# UART-Bluetooth.net
KiCad netlist of a schematic drawn in EAGLE
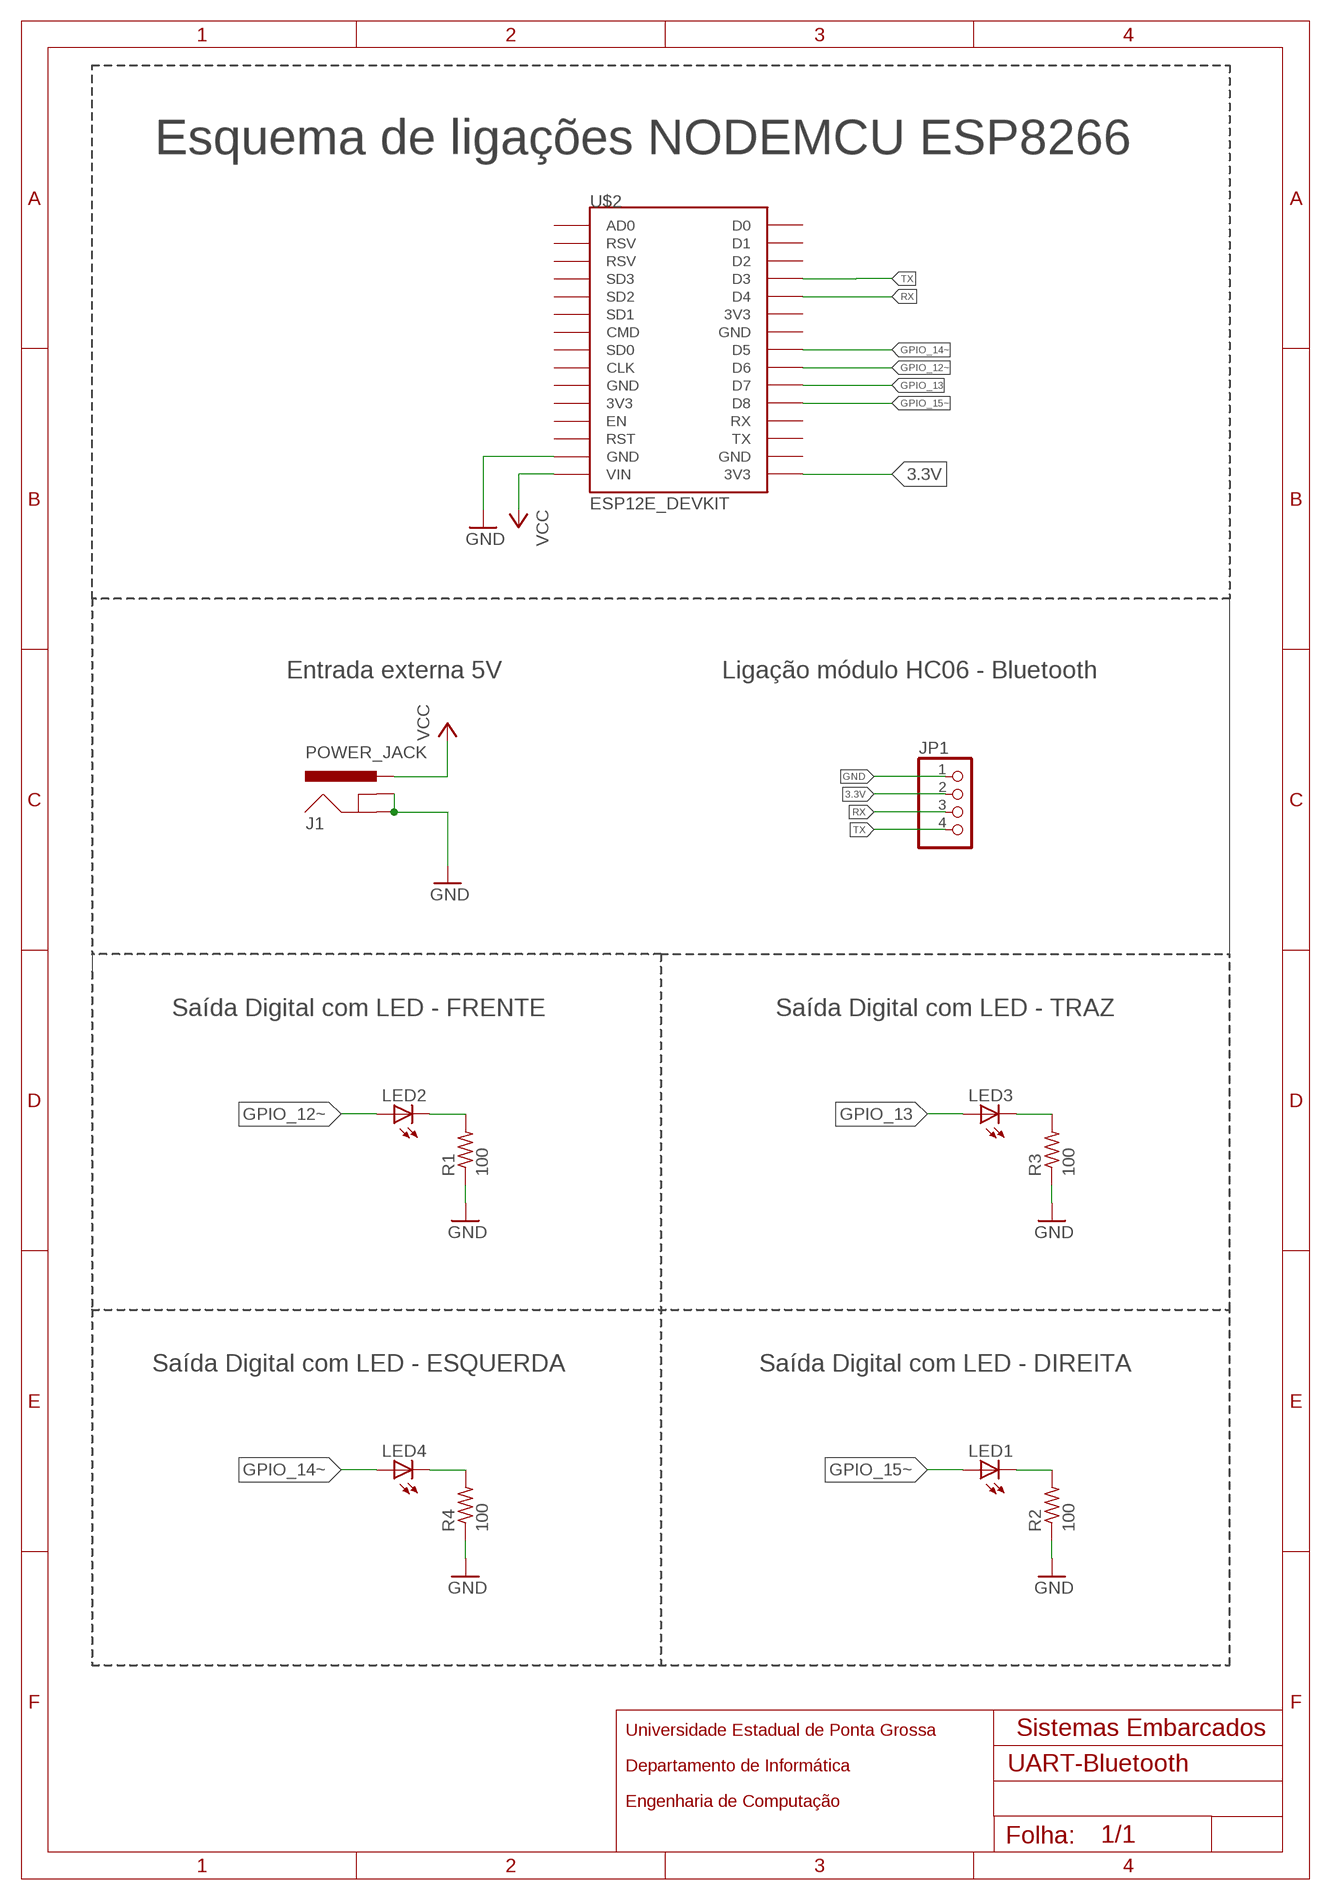
[diagram p0: schematic, sheet 1]

(export (version "E")
  (design (tool "Eeschema 10.0.6"))
  (components
    (comp (ref "J1")
      (value "POWER_JACK")
      (footprint "eagle-import:POWER_JACK_PTH")
      (libsource (lib "eagle-import") (part "POWER_JACK"))
    )
    (comp (ref "JP1")
      (value "PINHD-1X4")
      (footprint "eagle-import:1X04")
      (libsource (lib "eagle-import") (part "PINHD-1X4"))
    )
    (comp (ref "LED1")
      (value "LED5MM")
      (footprint "eagle-import:LED5MM")
      (libsource (lib "eagle-import") (part "LED5MM"))
    )
    (comp (ref "LED2")
      (value "LED5MM")
      (footprint "eagle-import:LED5MM")
      (libsource (lib "eagle-import") (part "LED5MM"))
    )
    (comp (ref "LED3")
      (value "LED5MM")
      (footprint "eagle-import:LED5MM")
      (libsource (lib "eagle-import") (part "LED5MM"))
    )
    (comp (ref "LED4")
      (value "LED5MM")
      (footprint "eagle-import:LED5MM")
      (libsource (lib "eagle-import") (part "LED5MM"))
    )
    (comp (ref "R1")
      (value "100")
      (footprint "eagle-import:0204_7")
      (libsource (lib "eagle-import") (part "R-US_0204/7"))
    )
    (comp (ref "R2")
      (value "100")
      (footprint "eagle-import:0204_7")
      (libsource (lib "eagle-import") (part "R-US_0204/7"))
    )
    (comp (ref "R3")
      (value "100")
      (footprint "eagle-import:0204_7")
      (libsource (lib "eagle-import") (part "R-US_0204/7"))
    )
    (comp (ref "R4")
      (value "100")
      (footprint "eagle-import:0204_7")
      (libsource (lib "eagle-import") (part "R-US_0204/7"))
    )
    (comp (ref "U$2")
      (value "ESP12E_DEVKIT")
      (footprint "eagle-import:ESP12E_DEVKIT")
      (libsource (lib "eagle-import") (part "ESP12E_DEVKIT"))
    )
  )
  (nets
    (net (code "1") (name "/GPIO_12~{}") (class "Default")
      (node (ref "LED2") (pin "A") (pinfunction "A_A") (pintype "passive"))
      (node (ref "U$2") (pin "D6") (pinfunction "D6_D6") (pintype "bidirectional"))
    )
    (net (code "2") (name "/GPIO_14~{}") (class "Default")
      (node (ref "LED4") (pin "A") (pinfunction "A_A") (pintype "passive"))
      (node (ref "U$2") (pin "D5") (pinfunction "D5_D5") (pintype "bidirectional"))
    )
    (net (code "3") (name "/GPIO_15~{}") (class "Default")
      (node (ref "LED1") (pin "A") (pinfunction "A_A") (pintype "passive"))
      (node (ref "U$2") (pin "D8") (pinfunction "D8_D8") (pintype "bidirectional"))
    )
    (net (code "4") (name "3.3V") (class "Default")
      (node (ref "JP1") (pin "2") (pinfunction "2_2") (pintype "passive"))
      (node (ref "U$2") (pin "3V3@2") (pinfunction "3V3_3V3@2") (pintype "bidirectional"))
    )
    (net (code "5") (name "GND") (class "Default")
      (node (ref "J1") (pin "GND") (pinfunction "GND_GND") (pintype "bidirectional"))
      (node (ref "J1") (pin "GNDBREAK") (pinfunction "GNDBREAK_GNDBREAK") (pintype "bidirectional"))
      (node (ref "JP1") (pin "1") (pinfunction "1_1") (pintype "passive"))
      (node (ref "R1") (pin "1") (pinfunction "1_1") (pintype "passive"))
      (node (ref "R2") (pin "1") (pinfunction "1_1") (pintype "passive"))
      (node (ref "R3") (pin "1") (pinfunction "1_1") (pintype "passive"))
      (node (ref "R4") (pin "1") (pinfunction "1_1") (pintype "passive"))
      (node (ref "U$2") (pin "GND@1") (pinfunction "GND_GND@1") (pintype "bidirectional"))
    )
    (net (code "6") (name "GPIO_13") (class "Default")
      (node (ref "LED3") (pin "A") (pinfunction "A_A") (pintype "passive"))
      (node (ref "U$2") (pin "D7") (pinfunction "D7_D7") (pintype "bidirectional"))
    )
    (net (code "7") (name "Net-(LED1-C)") (class "Default")
      (node (ref "LED1") (pin "K") (pinfunction "C_K") (pintype "passive"))
      (node (ref "R2") (pin "2") (pinfunction "2_2") (pintype "passive"))
    )
    (net (code "8") (name "Net-(LED2-C)") (class "Default")
      (node (ref "LED2") (pin "K") (pinfunction "C_K") (pintype "passive"))
      (node (ref "R1") (pin "2") (pinfunction "2_2") (pintype "passive"))
    )
    (net (code "9") (name "Net-(LED3-C)") (class "Default")
      (node (ref "LED3") (pin "K") (pinfunction "C_K") (pintype "passive"))
      (node (ref "R3") (pin "2") (pinfunction "2_2") (pintype "passive"))
    )
    (net (code "10") (name "Net-(LED4-C)") (class "Default")
      (node (ref "LED4") (pin "K") (pinfunction "C_K") (pintype "passive"))
      (node (ref "R4") (pin "2") (pinfunction "2_2") (pintype "passive"))
    )
    (net (code "11") (name "RX") (class "Default")
      (node (ref "JP1") (pin "3") (pinfunction "3_3") (pintype "passive"))
      (node (ref "U$2") (pin "D4") (pinfunction "D4_D4") (pintype "bidirectional"))
    )
    (net (code "12") (name "TX") (class "Default")
      (node (ref "JP1") (pin "4") (pinfunction "4_4") (pintype "passive"))
      (node (ref "U$2") (pin "D3") (pinfunction "D3_D3") (pintype "bidirectional"))
    )
    (net (code "13") (name "VCC") (class "Default")
      (node (ref "J1") (pin "PWR") (pinfunction "PWR_PWR") (pintype "bidirectional"))
      (node (ref "U$2") (pin "VIN") (pinfunction "VIN_VIN") (pintype "bidirectional"))
    )
    (net (code "14") (name "unconnected-(U$2-3V3-Pad3V3@0)") (class "Default")
      (node (ref "U$2") (pin "3V3@0") (pinfunction "3V3_3V3@0") (pintype "bidirectional"))
    )
    (net (code "15") (name "unconnected-(U$2-3V3-Pad3V3@1)") (class "Default")
      (node (ref "U$2") (pin "3V3@1") (pinfunction "3V3_3V3@1") (pintype "bidirectional"))
    )
    (net (code "16") (name "unconnected-(U$2-GND-PadGND@0)") (class "Default")
      (node (ref "U$2") (pin "GND@0") (pinfunction "GND_GND@0") (pintype "bidirectional"))
    )
    (net (code "17") (name "unconnected-(U$2-GND-PadGND@2)") (class "Default")
      (node (ref "U$2") (pin "GND@2") (pinfunction "GND_GND@2") (pintype "bidirectional"))
    )
    (net (code "18") (name "unconnected-(U$2-GND-PadGND@3)") (class "Default")
      (node (ref "U$2") (pin "GND@3") (pinfunction "GND_GND@3") (pintype "bidirectional"))
    )
    (net (code "19") (name "unconnected-(U$2-PadAD0)") (class "Default")
      (node (ref "U$2") (pin "AD0") (pinfunction "AD0_AD0") (pintype "bidirectional"))
    )
    (net (code "20") (name "unconnected-(U$2-PadCLK)") (class "Default")
      (node (ref "U$2") (pin "CLK") (pinfunction "CLK_CLK") (pintype "bidirectional"))
    )
    (net (code "21") (name "unconnected-(U$2-PadCMD)") (class "Default")
      (node (ref "U$2") (pin "CMD") (pinfunction "CMD_CMD") (pintype "bidirectional"))
    )
    (net (code "22") (name "unconnected-(U$2-PadD0)") (class "Default")
      (node (ref "U$2") (pin "D0") (pinfunction "D0_D0") (pintype "bidirectional"))
    )
    (net (code "23") (name "unconnected-(U$2-PadD1)") (class "Default")
      (node (ref "U$2") (pin "D1") (pinfunction "D1_D1") (pintype "bidirectional"))
    )
    (net (code "24") (name "unconnected-(U$2-PadD2)") (class "Default")
      (node (ref "U$2") (pin "D2") (pinfunction "D2_D2") (pintype "bidirectional"))
    )
    (net (code "25") (name "unconnected-(U$2-PadEN)") (class "Default")
      (node (ref "U$2") (pin "EN") (pinfunction "EN_EN") (pintype "bidirectional"))
    )
    (net (code "26") (name "unconnected-(U$2-PadRST)") (class "Default")
      (node (ref "U$2") (pin "RST") (pinfunction "RST_RST") (pintype "bidirectional"))
    )
    (net (code "27") (name "unconnected-(U$2-PadRX)") (class "Default")
      (node (ref "U$2") (pin "RX") (pinfunction "RX_RX") (pintype "bidirectional"))
    )
    (net (code "28") (name "unconnected-(U$2-PadSD0)") (class "Default")
      (node (ref "U$2") (pin "SD0") (pinfunction "SD0_SD0") (pintype "bidirectional"))
    )
    (net (code "29") (name "unconnected-(U$2-PadSD1)") (class "Default")
      (node (ref "U$2") (pin "SD1") (pinfunction "SD1_SD1") (pintype "bidirectional"))
    )
    (net (code "30") (name "unconnected-(U$2-PadSD2)") (class "Default")
      (node (ref "U$2") (pin "SD2") (pinfunction "SD2_SD2") (pintype "bidirectional"))
    )
    (net (code "31") (name "unconnected-(U$2-PadSD3)") (class "Default")
      (node (ref "U$2") (pin "SD3") (pinfunction "SD3_SD3") (pintype "bidirectional"))
    )
    (net (code "32") (name "unconnected-(U$2-PadTX)") (class "Default")
      (node (ref "U$2") (pin "TX") (pinfunction "TX_TX") (pintype "bidirectional"))
    )
    (net (code "33") (name "unconnected-(U$2-RSV-PadRSV@0)") (class "Default")
      (node (ref "U$2") (pin "RSV@0") (pinfunction "RSV_RSV@0") (pintype "bidirectional"))
    )
    (net (code "34") (name "unconnected-(U$2-RSV-PadRSV@1)") (class "Default")
      (node (ref "U$2") (pin "RSV@1") (pinfunction "RSV_RSV@1") (pintype "bidirectional"))
    )
  )
)
